# MC60.net
KiCad netlist of a schematic drawn in Altium Designer
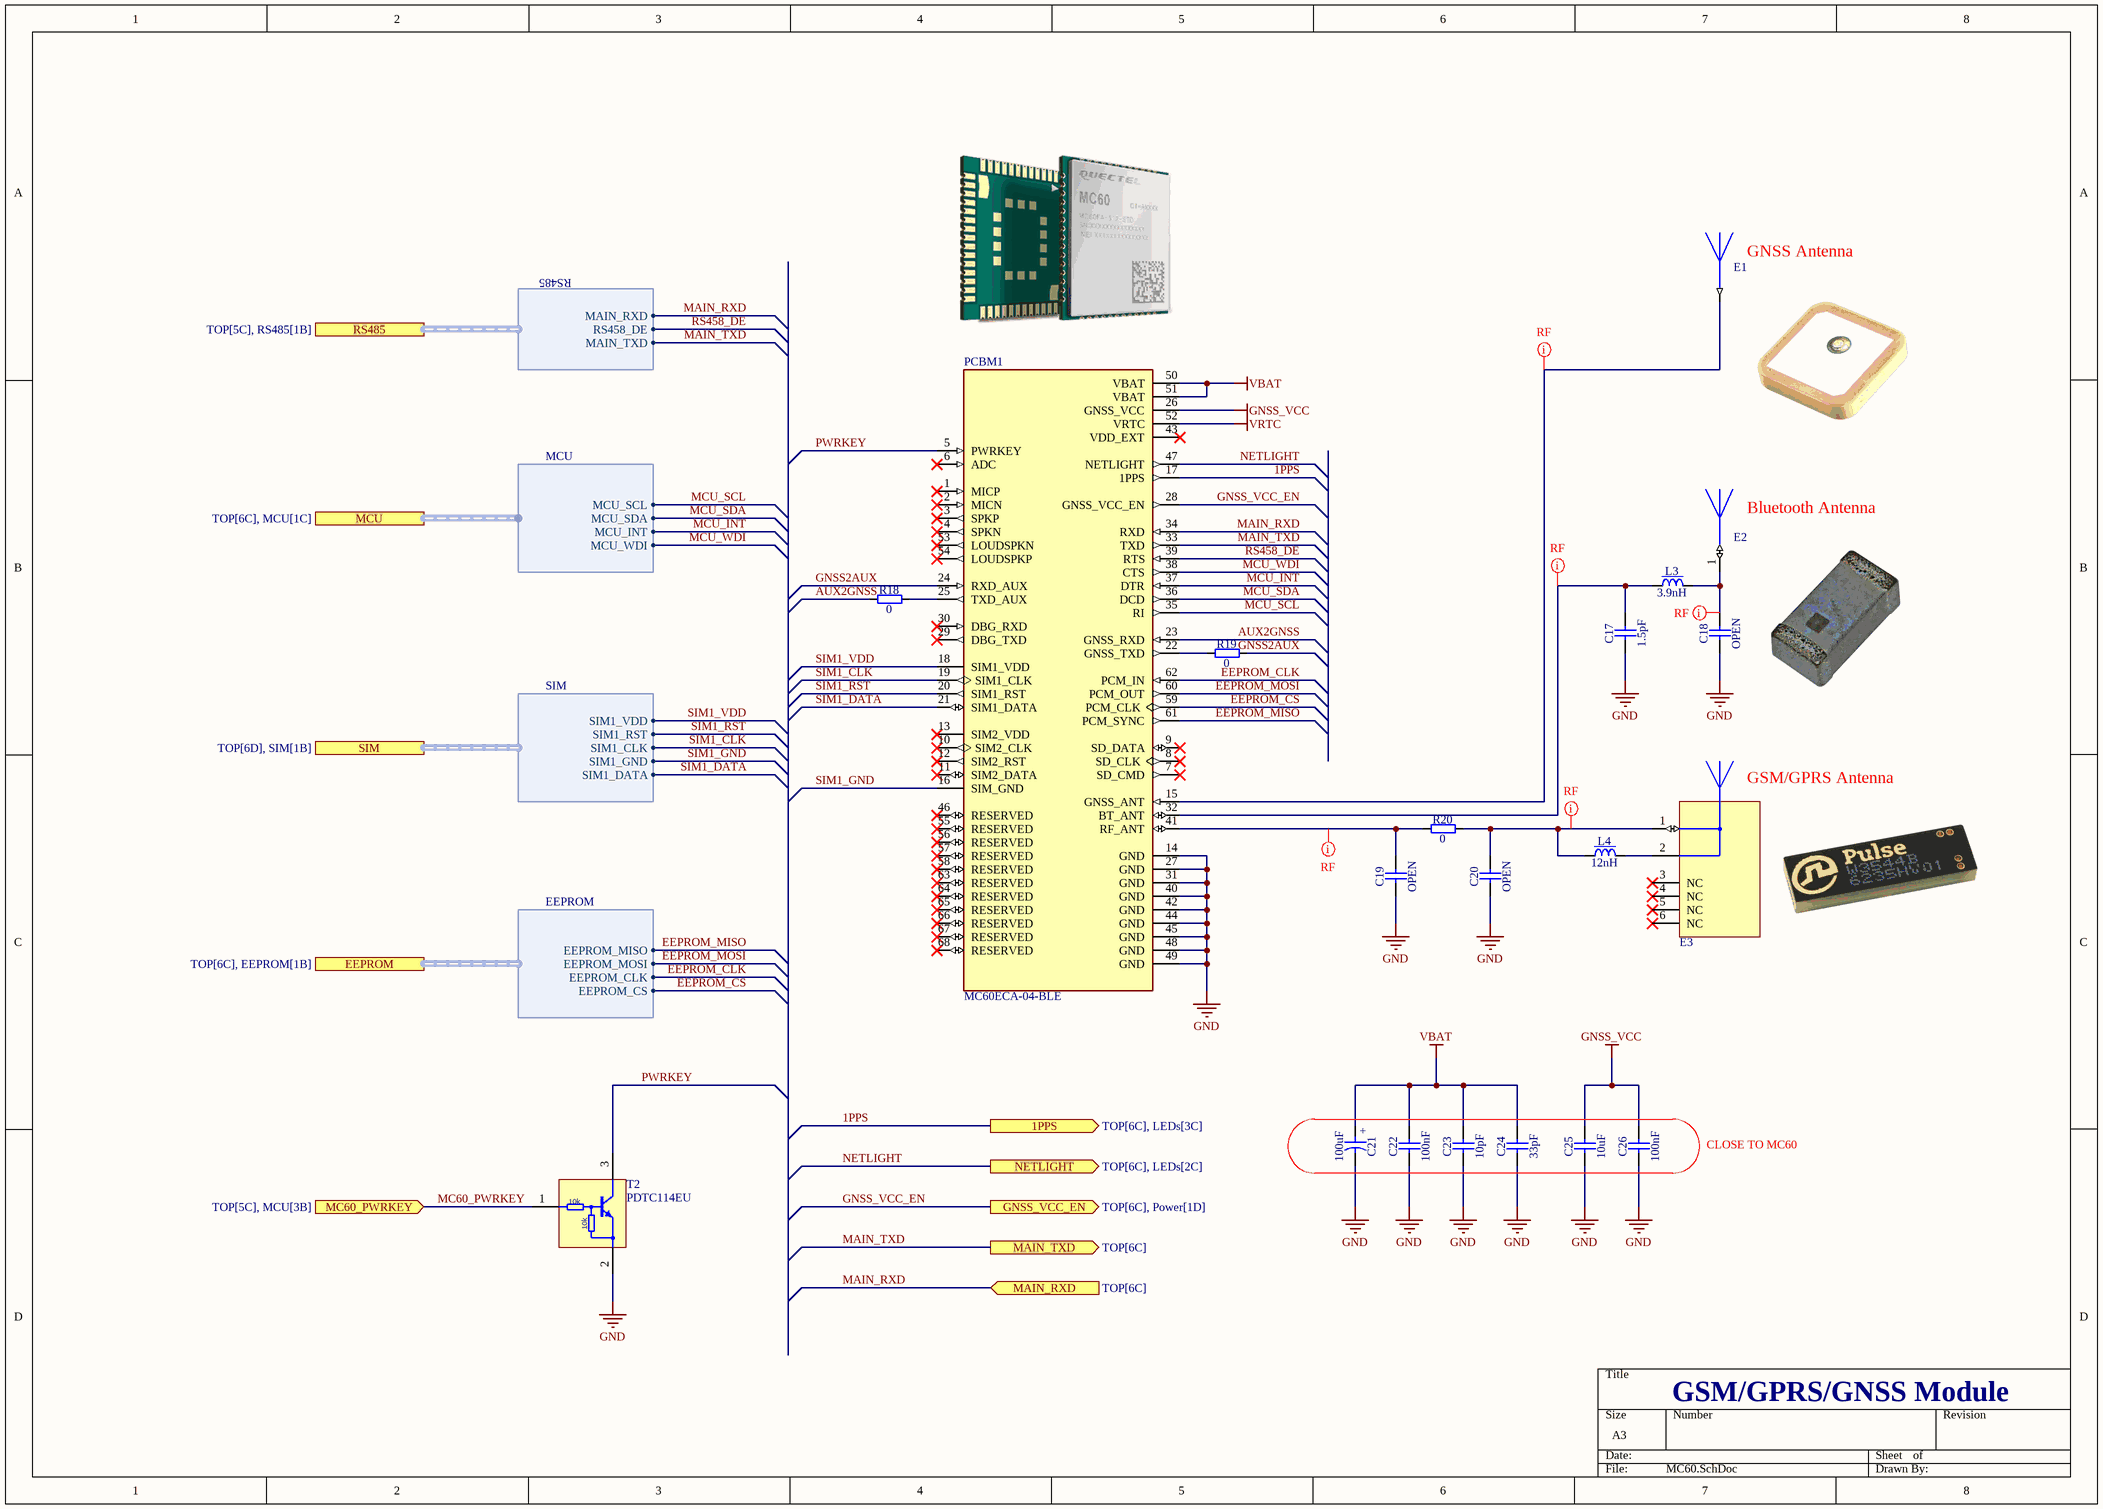
[diagram p0: MC60.SchDoc]

(export (version "E")
  (design (tool "Eeschema 10.0.6"))
  (components
    (comp (ref "C17")
      (value "1.5pF")
      (footprint "CAPC1005X55N")
      (description "Non-polarised capacitor")
      (fields
        (field (name "PART NUMBER") "CC0402_1.5PF_50V_0.25PF_C0G")
        (field (name "VOLTAGE") "50V")
        (field (name "AUTHOR") "CERN DEM JLC")
      )
      (libsource (lib "Capacitors") (part "Capacitor - non polarized"))
    )
    (comp (ref "C18")
      (value "OPEN")
      (footprint "CAPC1005X55N")
      (description "Non-polarised capacitor")
      (fields
        (field (name "PART NUMBER") "CC0402_0.2PF_50V_0.05PF_C0G_KEMET_HiQ-CBR")
        (field (name "VOLTAGE") "50V")
        (field (name "AUTHOR") "CERN DEM JLC")
      )
      (libsource (lib "Capacitors") (part "Capacitor - non polarized"))
    )
    (comp (ref "C19")
      (value "OPEN")
      (footprint "CAPC1005X55N")
      (description "Non-polarised capacitor")
      (fields
        (field (name "PART NUMBER") "CC0402_0.2PF_50V_0.05PF_C0G_KEMET_HiQ-CBR")
        (field (name "VOLTAGE") "50V")
        (field (name "AUTHOR") "CERN DEM JLC")
      )
      (libsource (lib "Capacitors") (part "Capacitor - non polarized"))
    )
    (comp (ref "C20")
      (value "OPEN")
      (footprint "CAPC1005X55N")
      (description "Non-polarised capacitor")
      (fields
        (field (name "PART NUMBER") "CC0402_0.2PF_50V_0.05PF_C0G_KEMET_HiQ-CBR")
        (field (name "VOLTAGE") "50V")
        (field (name "AUTHOR") "CERN DEM JLC")
      )
      (libsource (lib "Capacitors") (part "Capacitor - non polarized"))
    )
    (comp (ref "C21")
      (value "100uF")
      (footprint "CAPMP7343X310N")
      (description "Polarised capacitor")
      (fields
        (field (name "PART NUMBER") "CTE7343-31_100UF_10V_10%_LESR0050")
        (field (name "VOLTAGE") "10V")
        (field (name "AUTHOR") "CERN DEM JLC")
      )
      (libsource (lib "Capacitors") (part "Capacitor - polarized"))
    )
    (comp (ref "C22")
      (value "100nF")
      (footprint "CAPC1608X87N")
      (description "Non-polarised capacitor")
      (fields
        (field (name "PART NUMBER") "CC0603_100NF_50V_10%_X7R")
        (field (name "VOLTAGE") "50V")
        (field (name "AUTHOR") "CERN DEM JLC")
      )
      (libsource (lib "Capacitors") (part "Capacitor - non polarized"))
    )
    (comp (ref "C23")
      (value "10pF")
      (footprint "CAPC1608X87N")
      (description "Non-polarised capacitor")
      (fields
        (field (name "PART NUMBER") "CC0603_10PF_50V_5%_NP0")
        (field (name "VOLTAGE") "50V")
        (field (name "AUTHOR") "CERN DEM JLC")
      )
      (libsource (lib "Capacitors") (part "Capacitor - non polarized"))
    )
    (comp (ref "C24")
      (value "33pF")
      (footprint "CAPC1608X87N")
      (description "Non-polarised capacitor")
      (fields
        (field (name "PART NUMBER") "CC0603_33PF_50V_5%_NP0")
        (field (name "VOLTAGE") "50V")
        (field (name "AUTHOR") "CERN DEM JLC")
      )
      (libsource (lib "Capacitors") (part "Capacitor - non polarized"))
    )
    (comp (ref "C25")
      (value "10uF")
      (footprint "CAPC2012X135N")
      (description "Non-polarised capacitor")
      (fields
        (field (name "PART NUMBER") "CC0805_10UF_10V_10%_X7R")
        (field (name "VOLTAGE") "10V")
        (field (name "AUTHOR") "CERN DEM JLC")
      )
      (libsource (lib "Capacitors") (part "Capacitor - non polarized"))
    )
    (comp (ref "C26")
      (value "100nF")
      (footprint "CAPC1608X87N")
      (description "Non-polarised capacitor")
      (fields
        (field (name "PART NUMBER") "CC0603_100NF_50V_10%_X7R")
        (field (name "VOLTAGE") "50V")
        (field (name "AUTHOR") "CERN DEM JLC")
      )
      (libsource (lib "Capacitors") (part "Capacitor - non polarized"))
    )
    (comp (ref "E1")
      (value "APAE1590R2540AKDB1-T")
      (footprint "GPS_GLONASS_CERAMIC_25X25")
      (description "1.575GHz, 1.602GHz GLONASS, GPS Ceramic Patch RF Antenna 1.575GHz ~ 1.608GHz Pin Adhesive")
      (fields
        (field (name "MF") "Abracon LLC")
        (field (name "PART NUMBER") "ABRACON_APAE1590R2540AKDB1-T")
        (field (name "AUTHOR") "Xusniyor")
      )
      (libsource (lib "Eletro-mechanical") (part "GPS_GLONASS_ANTENNA"))
    )
    (comp (ref "E2")
      (value "AMCA31-2R450G-S1F-T3")
      (footprint "AMCA31-2R450G-S1F-T3")
      (description "2.4GHz Bluetooth, Wi-Fi, WLAN Chip RF Antenna 2.405GHz ~ 2.495GHz 0.5dBi Solder Surface Mount")
      (fields (field (name "MF") "Abracon LLC") (field (name "AUTHOR") "Xusniyor"))
      (libsource (lib "Eletro-mechanical") (part "AMCA31-2R450G-S1F-T3"))
    )
    (comp (ref "E3")
      (value "W3544B")
      (footprint "PULSE_ELECTRONICS_W3544X")
      (fields
        (field (name "PART NUMBER") "PULSE_ELECTRONICS_W3544X")
        (field (name "MANUFACTURER") "Pulse Electronics")
        (field (name "AUTHOR") "Xusniyor")
      )
      (libsource (lib "Eletro-mechanical") (part "PULSE_ELECTRONICS_W3544X"))
    )
    (comp (ref "L3")
      (value "3.9nH")
      (footprint "IND_MURATA_LQW18AS_0Z")
      (description "Inductor With Core")
      (fields
        (field (name "PART NUMBER") "IND0603_12NH_5%_MURATA_LQW18AN3N9D00D")
        (field (name "POWER") "850mA")
        (field (name "AUTHOR") "Xusniyor")
      )
      (libsource (lib "Inductors & Transformers") (part "Inductor With Magnetic core"))
    )
    (comp (ref "L4")
      (value "12nH")
      (footprint "IND_MURATA_LQW18AS_0Z")
      (description "Inductor With Core")
      (fields
        (field (name "PART NUMBER") "IND0603_12NH_5%_MURATA_LQW18AN12NJ00D")
        (field (name "POWER") "600mA")
        (field (name "AUTHOR") "Xusniyor")
      )
      (libsource (lib "Inductors & Transformers") (part "Inductor With Magnetic core"))
    )
    (comp (ref "PCBM1")
      (value "MC60ECA-04-BLE")
      (footprint "PCBM_QUECTEL_MC60")
      (fields (field (name "MF") "Quectel") (field (name "AUTHOR") "Xusniyor"))
      (libsource (lib "ICs And Semiconductors") (part "PCBM_QUECTEL_MC60"))
    )
    (comp (ref "R18")
      (value "0")
      (footprint "RESC1608X55N")
      (description "Resistor")
      (fields
        (field (name "PART NUMBER") "R0603_0R_JUMPER")
        (field (name "MANUFACTURER") "GENERIC")
        (field (name "AUTHOR") "CERN DEM JLC")
      )
      (libsource (lib "Resistors") (part "Resistor"))
    )
    (comp (ref "R19")
      (value "0")
      (footprint "RESC1608X55N")
      (description "Resistor")
      (fields
        (field (name "PART NUMBER") "R0603_0R_JUMPER")
        (field (name "MANUFACTURER") "GENERIC")
        (field (name "AUTHOR") "CERN DEM JLC")
      )
      (libsource (lib "Resistors") (part "Resistor"))
    )
    (comp (ref "R20")
      (value "0")
      (footprint "RESC1005X40N")
      (description "Resistor")
      (fields
        (field (name "PART NUMBER") "R0402_0R_JUMPER")
        (field (name "MANUFACTURER") "GENERIC")
        (field (name "AUTHOR") "CERN DEM JLC")
      )
      (libsource (lib "Resistors") (part "Resistor"))
    )
    (comp (ref "T2")
      (value "PDTC114EU")
      (footprint "SOT65P210X100-3N")
      (description "Pre-Biased Bipolar Transistor (BJT) NPN - Pre-Biased 50 V 100 mA 200 mW Surface Mount SOT-323")
      (fields (field (name "MANUFACTURER") "Nexperia USA Inc.") (field (name "AUTHOR") "Xusniyor"))
      (libsource (lib "ICs And Semiconductors") (part "PDTC114EU"))
    )
  )
  (nets
    (net (code "5") (name "/1PPS") (class "Default")
      (node (ref "PCBM1") (pin "17") (pinfunction "1PPS_17") (pintype "output"))
    )
    (net (code "6") (name "/AUX2GNSS") (class "Default")
      (node (ref "PCBM1") (pin "23") (pinfunction "GNSS_RXD_23") (pintype "input"))
      (node (ref "R18") (pin "1") (pinfunction "1_1") (pintype "passive"))
    )
    (net (code "7") (name "/EEPROM_CLK") (class "Default")
      (node (ref "PCBM1") (pin "62") (pinfunction "PCM_IN_62") (pintype "input"))
    )
    (net (code "8") (name "/EEPROM_CS") (class "Default")
      (node (ref "PCBM1") (pin "59") (pinfunction "PCM_CLK_59") (pintype "output"))
    )
    (net (code "9") (name "/EEPROM_MISO") (class "Default")
      (node (ref "PCBM1") (pin "61") (pinfunction "PCM_SYNC_61") (pintype "output"))
    )
    (net (code "10") (name "/EEPROM_MOSI") (class "Default")
      (node (ref "PCBM1") (pin "60") (pinfunction "PCM_OUT_60") (pintype "output"))
    )
    (net (code "11") (name "/GNSS2AUX") (class "Default")
      (node (ref "PCBM1") (pin "24") (pinfunction "RXD_AUX_24") (pintype "input"))
      (node (ref "R19") (pin "2") (pinfunction "2_2") (pintype "passive"))
    )
    (net (code "12") (name "/GNSS_VCC_EN") (class "Default")
      (node (ref "PCBM1") (pin "28") (pinfunction "GNSS_VCC_EN_28") (pintype "output"))
    )
    (net (code "13") (name "/MAIN_RXD") (class "Default")
      (node (ref "PCBM1") (pin "34") (pinfunction "RXD_34") (pintype "input"))
    )
    (net (code "14") (name "/MAIN_TXD") (class "Default")
      (node (ref "PCBM1") (pin "33") (pinfunction "TXD_33") (pintype "output"))
    )
    (net (code "15") (name "/MC60_PWRKEY") (class "Default")
      (node (ref "T2") (pin "1") (pinfunction "B_1") (pintype "passive"))
    )
    (net (code "16") (name "/MCU_INT") (class "Default")
      (node (ref "PCBM1") (pin "37") (pinfunction "DTR_37") (pintype "input"))
    )
    (net (code "17") (name "/MCU_SCL") (class "Default")
      (node (ref "PCBM1") (pin "35") (pinfunction "RI_35") (pintype "output"))
    )
    (net (code "18") (name "/MCU_SDA") (class "Default")
      (node (ref "PCBM1") (pin "36") (pinfunction "DCD_36") (pintype "output"))
    )
    (net (code "19") (name "/MCU_WDI") (class "Default")
      (node (ref "PCBM1") (pin "38") (pinfunction "CTS_38") (pintype "output"))
    )
    (net (code "20") (name "/NETLIGHT") (class "Default")
      (node (ref "PCBM1") (pin "47") (pinfunction "NETLIGHT_47") (pintype "output"))
    )
    (net (code "21") (name "/PWRKEY") (class "Default")
      (node (ref "PCBM1") (pin "5") (pinfunction "PWRKEY_5") (pintype "input"))
      (node (ref "T2") (pin "3") (pinfunction "C_3") (pintype "passive"))
    )
    (net (code "22") (name "/RS458_DE") (class "Default")
      (node (ref "PCBM1") (pin "39") (pinfunction "RTS_39") (pintype "input"))
    )
    (net (code "23") (name "/SIM1_CLK") (class "Default")
      (node (ref "PCBM1") (pin "19") (pinfunction "SIM1_CLK_19") (pintype "output"))
    )
    (net (code "24") (name "/SIM1_DATA") (class "Default")
      (node (ref "PCBM1") (pin "21") (pinfunction "SIM1_DATA_21") (pintype "bidirectional"))
    )
    (net (code "25") (name "/SIM1_GND") (class "Default")
      (node (ref "PCBM1") (pin "16") (pinfunction "SIM_GND_16") (pintype "power_in"))
    )
    (net (code "26") (name "/SIM1_RST") (class "Default")
      (node (ref "PCBM1") (pin "20") (pinfunction "SIM1_RST_20") (pintype "output"))
    )
    (net (code "27") (name "/SIM1_VDD") (class "Default")
      (node (ref "PCBM1") (pin "18") (pinfunction "SIM1_VDD_18") (pintype "power_in"))
    )
    (net (code "32") (name "GND") (class "Default")
      (node (ref "C17") (pin "1") (pinfunction "1_1") (pintype "passive"))
      (node (ref "C18") (pin "1") (pinfunction "1_1") (pintype "passive"))
      (node (ref "C19") (pin "1") (pinfunction "1_1") (pintype "passive"))
      (node (ref "C20") (pin "1") (pinfunction "1_1") (pintype "passive"))
      (node (ref "C21") (pin "2") (pinfunction "2_2") (pintype "passive"))
      (node (ref "C22") (pin "1") (pinfunction "1_1") (pintype "passive"))
      (node (ref "C23") (pin "1") (pinfunction "1_1") (pintype "passive"))
      (node (ref "C24") (pin "1") (pinfunction "1_1") (pintype "passive"))
      (node (ref "C25") (pin "1") (pinfunction "1_1") (pintype "passive"))
      (node (ref "C26") (pin "1") (pinfunction "1_1") (pintype "passive"))
      (node (ref "PCBM1") (pin "14") (pinfunction "GND_14") (pintype "power_in"))
      (node (ref "PCBM1") (pin "27") (pinfunction "GND_27") (pintype "power_in"))
      (node (ref "PCBM1") (pin "31") (pinfunction "GND_31") (pintype "power_in"))
      (node (ref "PCBM1") (pin "40") (pinfunction "GND_40") (pintype "power_in"))
      (node (ref "PCBM1") (pin "42") (pinfunction "GND_42") (pintype "power_in"))
      (node (ref "PCBM1") (pin "44") (pinfunction "GND_44") (pintype "power_in"))
      (node (ref "PCBM1") (pin "45") (pinfunction "GND_45") (pintype "power_in"))
      (node (ref "PCBM1") (pin "48") (pinfunction "GND_48") (pintype "power_in"))
      (node (ref "PCBM1") (pin "49") (pinfunction "GND_49") (pintype "power_in"))
      (node (ref "T2") (pin "2") (pinfunction "E_2") (pintype "passive"))
    )
    (net (code "33") (name "GNSS_VCC") (class "Default")
      (node (ref "C25") (pin "2") (pinfunction "2_2") (pintype "passive"))
      (node (ref "C26") (pin "2") (pinfunction "2_2") (pintype "passive"))
      (node (ref "PCBM1") (pin "26") (pinfunction "GNSS_VCC_26") (pintype "power_in"))
    )
    (net (code "34") (name "Net-(C18-Pad2)") (class "Default")
      (node (ref "C18") (pin "2") (pinfunction "2_2") (pintype "passive"))
      (node (ref "E2") (pin "1") (pinfunction "1_1") (pintype "bidirectional"))
      (node (ref "L3") (pin "2") (pinfunction "2_2") (pintype "passive"))
    )
    (net (code "35") (name "Net-(C20-Pad2)") (class "Default")
      (node (ref "C20") (pin "2") (pinfunction "2_2") (pintype "passive"))
      (node (ref "E3") (pin "1") (pintype "bidirectional"))
      (node (ref "L4") (pin "1") (pinfunction "1_1") (pintype "passive"))
      (node (ref "R20") (pin "2") (pinfunction "2_2") (pintype "passive"))
    )
    (net (code "36") (name "Net-(E3-Pad2)") (class "Default")
      (node (ref "E3") (pin "2") (pintype "passive"))
      (node (ref "L4") (pin "2") (pinfunction "2_2") (pintype "passive"))
    )
    (net (code "37") (name "Net-(PCBM1-BT_ANT)") (class "Default")
      (node (ref "C17") (pin "2") (pinfunction "2_2") (pintype "passive"))
      (node (ref "L3") (pin "1") (pinfunction "1_1") (pintype "passive"))
      (node (ref "PCBM1") (pin "32") (pinfunction "BT_ANT_32") (pintype "bidirectional"))
    )
    (net (code "38") (name "Net-(PCBM1-GNSS_ANT)") (class "Default")
      (node (ref "E1") (pin "1") (pintype "output"))
      (node (ref "PCBM1") (pin "15") (pinfunction "GNSS_ANT_15") (pintype "input"))
    )
    (net (code "39") (name "Net-(PCBM1-GNSS_TXD)") (class "Default")
      (node (ref "PCBM1") (pin "22") (pinfunction "GNSS_TXD_22") (pintype "output"))
      (node (ref "R19") (pin "1") (pinfunction "1_1") (pintype "passive"))
    )
    (net (code "40") (name "Net-(PCBM1-RF_ANT)") (class "Default")
      (node (ref "C19") (pin "2") (pinfunction "2_2") (pintype "passive"))
      (node (ref "PCBM1") (pin "41") (pinfunction "RF_ANT_41") (pintype "bidirectional"))
      (node (ref "R20") (pin "1") (pinfunction "1_1") (pintype "passive"))
    )
    (net (code "41") (name "Net-(PCBM1-TXD_AUX)") (class "Default")
      (node (ref "PCBM1") (pin "25") (pinfunction "TXD_AUX_25") (pintype "output"))
      (node (ref "R18") (pin "2") (pinfunction "2_2") (pintype "passive"))
    )
    (net (code "42") (name "VBAT") (class "Default")
      (node (ref "C21") (pin "1") (pinfunction "1_1") (pintype "passive"))
      (node (ref "C22") (pin "2") (pinfunction "2_2") (pintype "passive"))
      (node (ref "C23") (pin "2") (pinfunction "2_2") (pintype "passive"))
      (node (ref "C24") (pin "2") (pinfunction "2_2") (pintype "passive"))
      (node (ref "PCBM1") (pin "50") (pinfunction "VBAT_50") (pintype "power_in"))
      (node (ref "PCBM1") (pin "51") (pinfunction "VBAT_51") (pintype "power_in"))
    )
    (net (code "43") (name "VRTC") (class "Default")
      (node (ref "PCBM1") (pin "52") (pinfunction "VRTC_52") (pintype "power_in"))
    )
    (net (code "44") (name "unconnected-(E3-NC-Pad3)") (class "Default")
      (node (ref "E3") (pin "3") (pinfunction "NC_3") (pintype "passive+no_connect"))
    )
    (net (code "45") (name "unconnected-(E3-NC-Pad4)") (class "Default")
      (node (ref "E3") (pin "4") (pinfunction "NC_4") (pintype "passive+no_connect"))
    )
    (net (code "46") (name "unconnected-(E3-NC-Pad5)") (class "Default")
      (node (ref "E3") (pin "5") (pinfunction "NC_5") (pintype "passive+no_connect"))
    )
    (net (code "47") (name "unconnected-(E3-NC-Pad6)") (class "Default")
      (node (ref "E3") (pin "6") (pinfunction "NC_6") (pintype "passive+no_connect"))
    )
    (net (code "48") (name "unconnected-(PCBM1-ADC-Pad6)") (class "Default")
      (node (ref "PCBM1") (pin "6") (pinfunction "ADC_6") (pintype "input+no_connect"))
    )
    (net (code "49") (name "unconnected-(PCBM1-DBG_RXD-Pad30)") (class "Default")
      (node (ref "PCBM1") (pin "30") (pinfunction "DBG_RXD_30") (pintype "input+no_connect"))
    )
    (net (code "50") (name "unconnected-(PCBM1-DBG_TXD-Pad29)") (class "Default")
      (node (ref "PCBM1") (pin "29") (pinfunction "DBG_TXD_29") (pintype "output+no_connect"))
    )
    (net (code "51") (name "unconnected-(PCBM1-LOUDSPKN-Pad53)") (class "Default")
      (node (ref "PCBM1") (pin "53") (pinfunction "LOUDSPKN_53") (pintype "output+no_connect"))
    )
    (net (code "52") (name "unconnected-(PCBM1-LOUDSPKP-Pad54)") (class "Default")
      (node (ref "PCBM1") (pin "54") (pinfunction "LOUDSPKP_54") (pintype "output+no_connect"))
    )
    (net (code "53") (name "unconnected-(PCBM1-MICN-Pad2)") (class "Default")
      (node (ref "PCBM1") (pin "2") (pinfunction "MICN_2") (pintype "input+no_connect"))
    )
    (net (code "54") (name "unconnected-(PCBM1-MICP-Pad1)") (class "Default")
      (node (ref "PCBM1") (pin "1") (pinfunction "MICP_1") (pintype "input+no_connect"))
    )
    (net (code "55") (name "unconnected-(PCBM1-RESERVED-Pad46)") (class "Default")
      (node (ref "PCBM1") (pin "46") (pinfunction "RESERVED_46") (pintype "bidirectional+no_connect"))
    )
    (net (code "56") (name "unconnected-(PCBM1-RESERVED-Pad55)") (class "Default")
      (node (ref "PCBM1") (pin "55") (pinfunction "RESERVED_55") (pintype "bidirectional+no_connect"))
    )
    (net (code "57") (name "unconnected-(PCBM1-RESERVED-Pad56)") (class "Default")
      (node (ref "PCBM1") (pin "56") (pinfunction "RESERVED_56") (pintype "bidirectional+no_connect"))
    )
    (net (code "58") (name "unconnected-(PCBM1-RESERVED-Pad57)") (class "Default")
      (node (ref "PCBM1") (pin "57") (pinfunction "RESERVED_57") (pintype "bidirectional+no_connect"))
    )
    (net (code "59") (name "unconnected-(PCBM1-RESERVED-Pad58)") (class "Default")
      (node (ref "PCBM1") (pin "58") (pinfunction "RESERVED_58") (pintype "bidirectional+no_connect"))
    )
    (net (code "60") (name "unconnected-(PCBM1-RESERVED-Pad63)") (class "Default")
      (node (ref "PCBM1") (pin "63") (pinfunction "RESERVED_63") (pintype "bidirectional+no_connect"))
    )
    (net (code "61") (name "unconnected-(PCBM1-RESERVED-Pad64)") (class "Default")
      (node (ref "PCBM1") (pin "64") (pinfunction "RESERVED_64") (pintype "bidirectional+no_connect"))
    )
    (net (code "62") (name "unconnected-(PCBM1-RESERVED-Pad65)") (class "Default")
      (node (ref "PCBM1") (pin "65") (pinfunction "RESERVED_65") (pintype "bidirectional+no_connect"))
    )
    (net (code "63") (name "unconnected-(PCBM1-RESERVED-Pad66)") (class "Default")
      (node (ref "PCBM1") (pin "66") (pinfunction "RESERVED_66") (pintype "bidirectional+no_connect"))
    )
    (net (code "64") (name "unconnected-(PCBM1-RESERVED-Pad67)") (class "Default")
      (node (ref "PCBM1") (pin "67") (pinfunction "RESERVED_67") (pintype "bidirectional+no_connect"))
    )
    (net (code "65") (name "unconnected-(PCBM1-RESERVED-Pad68)") (class "Default")
      (node (ref "PCBM1") (pin "68") (pinfunction "RESERVED_68") (pintype "bidirectional+no_connect"))
    )
    (net (code "66") (name "unconnected-(PCBM1-SD_CLK-Pad8)") (class "Default")
      (node (ref "PCBM1") (pin "8") (pinfunction "SD_CLK_8") (pintype "output+no_connect"))
    )
    (net (code "67") (name "unconnected-(PCBM1-SD_CMD-Pad7)") (class "Default")
      (node (ref "PCBM1") (pin "7") (pinfunction "SD_CMD_7") (pintype "output+no_connect"))
    )
    (net (code "68") (name "unconnected-(PCBM1-SD_DATA-Pad9)") (class "Default")
      (node (ref "PCBM1") (pin "9") (pinfunction "SD_DATA_9") (pintype "bidirectional+no_connect"))
    )
    (net (code "69") (name "unconnected-(PCBM1-SIM2_CLK-Pad10)") (class "Default")
      (node (ref "PCBM1") (pin "10") (pinfunction "SIM2_CLK_10") (pintype "output+no_connect"))
    )
    (net (code "70") (name "unconnected-(PCBM1-SIM2_DATA-Pad11)") (class "Default")
      (node (ref "PCBM1") (pin "11") (pinfunction "SIM2_DATA_11") (pintype "bidirectional+no_connect"))
    )
    (net (code "71") (name "unconnected-(PCBM1-SIM2_RST-Pad12)") (class "Default")
      (node (ref "PCBM1") (pin "12") (pinfunction "SIM2_RST_12") (pintype "output+no_connect"))
    )
    (net (code "72") (name "unconnected-(PCBM1-SIM2_VDD-Pad13)") (class "Default")
      (node (ref "PCBM1") (pin "13") (pinfunction "SIM2_VDD_13") (pintype "power_in+no_connect"))
    )
    (net (code "73") (name "unconnected-(PCBM1-SPKN-Pad4)") (class "Default")
      (node (ref "PCBM1") (pin "4") (pinfunction "SPKN_4") (pintype "output+no_connect"))
    )
    (net (code "74") (name "unconnected-(PCBM1-SPKP-Pad3)") (class "Default")
      (node (ref "PCBM1") (pin "3") (pinfunction "SPKP_3") (pintype "output+no_connect"))
    )
    (net (code "75") (name "unconnected-(PCBM1-VDD_EXT-Pad43)") (class "Default")
      (node (ref "PCBM1") (pin "43") (pinfunction "VDD_EXT_43") (pintype "power_in+no_connect"))
    )
  )
)
